# dual_vca_main.net
KiCad netlist of a schematic drawn in EAGLE
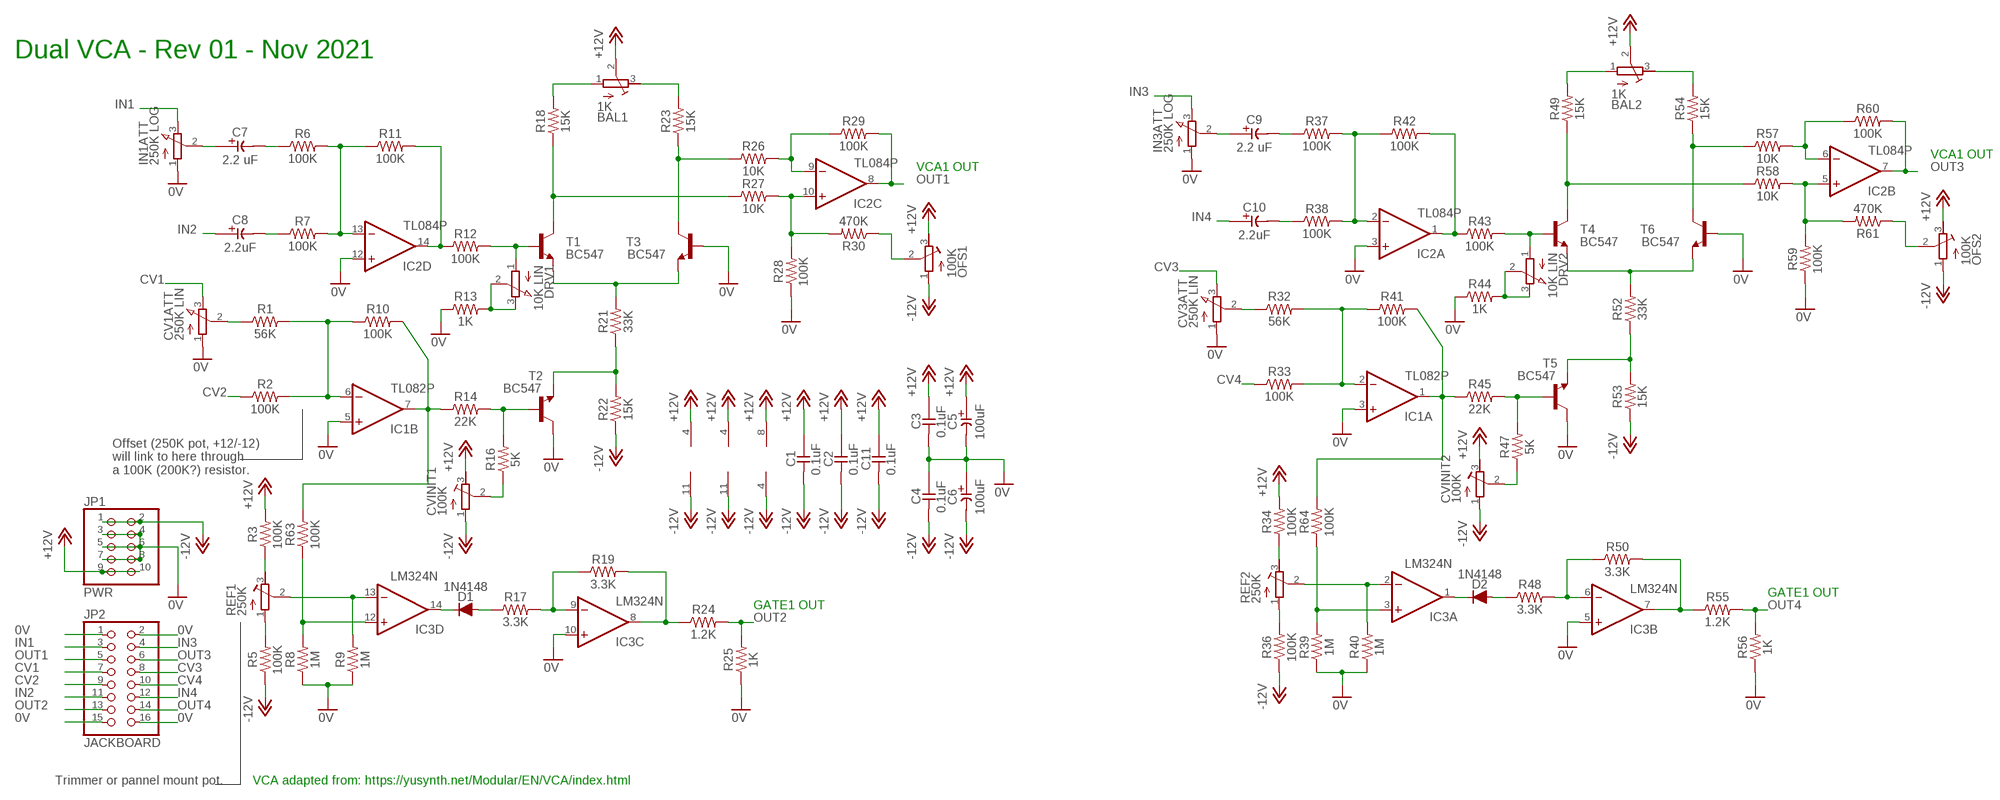
[diagram p0: schematic, sheet 1]

(export (version "E")
  (design (tool "Eeschema 10.0.6"))
  (components
    (comp (ref "BAL1")
      (value "1K")
      (footprint "eagle-import:RTRIM3339P")
      (libsource (lib "eagle-import") (part "R-TRIMM3339P"))
    )
    (comp (ref "BAL2")
      (value "1K")
      (footprint "eagle-import:RTRIM3339P")
      (libsource (lib "eagle-import") (part "R-TRIMM3339P"))
    )
    (comp (ref "C1")
      (value "0.1uF")
      (footprint "eagle-import:C025-024X044")
      (libsource (lib "eagle-import") (part "CC-US025-024X044"))
    )
    (comp (ref "C2")
      (value "0.1uF")
      (footprint "eagle-import:C025-024X044")
      (libsource (lib "eagle-import") (part "CC-US025-024X044"))
    )
    (comp (ref "C3")
      (value "0.1uF")
      (footprint "eagle-import:C025-024X044")
      (libsource (lib "eagle-import") (part "CC-US025-024X044"))
    )
    (comp (ref "C4")
      (value "0.1uF")
      (footprint "eagle-import:C025-024X044")
      (libsource (lib "eagle-import") (part "CC-US025-024X044"))
    )
    (comp (ref "C5")
      (value "100uF")
      (footprint "eagle-import:E5-8,5")
      (libsource (lib "eagle-import") (part "CE-USE5-8.5"))
    )
    (comp (ref "C6")
      (value "100uF")
      (footprint "eagle-import:E5-8,5")
      (libsource (lib "eagle-import") (part "CE-USE5-8.5"))
    )
    (comp (ref "C7")
      (value "2.2 uF")
      (footprint "eagle-import:E2-5")
      (libsource (lib "eagle-import") (part "CE-USE2-5"))
    )
    (comp (ref "C8")
      (value "2.2uF")
      (footprint "eagle-import:E2-5")
      (libsource (lib "eagle-import") (part "CE-USE2-5"))
    )
    (comp (ref "C9")
      (value "2.2 uF")
      (footprint "eagle-import:E2-5")
      (libsource (lib "eagle-import") (part "CE-USE2-5"))
    )
    (comp (ref "C10")
      (value "2.2uF")
      (footprint "eagle-import:E2-5")
      (libsource (lib "eagle-import") (part "CE-USE2-5"))
    )
    (comp (ref "C11")
      (value "0.1uF")
      (footprint "eagle-import:C025-024X044")
      (libsource (lib "eagle-import") (part "CC-US025-024X044"))
    )
    (comp (ref "CV1ATT")
      (value "250K LIN")
      (footprint "eagle-import:3RP_1610N")
      (libsource (lib "eagle-import") (part "3RP/1610N"))
    )
    (comp (ref "CV3ATT")
      (value "250K LIN")
      (footprint "eagle-import:3RP_1610N")
      (libsource (lib "eagle-import") (part "3RP/1610N"))
    )
    (comp (ref "CVINIT1")
      (value "100K")
      (footprint "eagle-import:RTRIM3339P")
      (libsource (lib "eagle-import") (part "R-TRIMM3339P"))
    )
    (comp (ref "CVINIT2")
      (value "100K")
      (footprint "eagle-import:RTRIM3339P")
      (libsource (lib "eagle-import") (part "R-TRIMM3339P"))
    )
    (comp (ref "D1")
      (value "1N4148")
      (footprint "eagle-import:DO34-5")
      (libsource (lib "eagle-import") (part "1N4148"))
    )
    (comp (ref "D2")
      (value "1N4148")
      (footprint "eagle-import:DO34-5")
      (libsource (lib "eagle-import") (part "1N4148"))
    )
    (comp (ref "DRV1")
      (value "10K LIN")
      (footprint "eagle-import:3RP_1610N")
      (libsource (lib "eagle-import") (part "3RP/1610N"))
    )
    (comp (ref "DRV2")
      (value "10K LIN")
      (footprint "eagle-import:3RP_1610N")
      (libsource (lib "eagle-import") (part "3RP/1610N"))
    )
    (comp (ref "IC1")
      (value "TL082P")
      (footprint "eagle-import:DIL08")
      (libsource (lib "eagle-import") (part "TL082P"))
    )
    (comp (ref "IC2")
      (value "TL084P")
      (footprint "eagle-import:DIL14")
      (libsource (lib "eagle-import") (part "TL084P"))
    )
    (comp (ref "IC3")
      (value "LM324N")
      (footprint "eagle-import:DIL14")
      (libsource (lib "eagle-import") (part "LM324N"))
    )
    (comp (ref "IN1ATT")
      (value "250K LOG")
      (footprint "eagle-import:3RP_1610N")
      (libsource (lib "eagle-import") (part "3RP/1610N"))
    )
    (comp (ref "IN3ATT")
      (value "250K LOG")
      (footprint "eagle-import:3RP_1610N")
      (libsource (lib "eagle-import") (part "3RP/1610N"))
    )
    (comp (ref "JP1")
      (value "PWR")
      (footprint "eagle-import:2X05")
      (libsource (lib "eagle-import") (part "PINHD-2X5"))
    )
    (comp (ref "JP2")
      (value "JACKBOARD")
      (footprint "eagle-import:2X08")
      (libsource (lib "eagle-import") (part "PINHD-2X8"))
    )
    (comp (ref "OFS1")
      (value "100K")
      (footprint "eagle-import:RTRIM3339P")
      (libsource (lib "eagle-import") (part "R-TRIMM3339P"))
    )
    (comp (ref "OFS2")
      (value "100K")
      (footprint "eagle-import:RTRIM3339P")
      (libsource (lib "eagle-import") (part "R-TRIMM3339P"))
    )
    (comp (ref "R1")
      (value "56K")
      (footprint "eagle-import:0207_7")
      (libsource (lib "eagle-import") (part "R"))
    )
    (comp (ref "R2")
      (value "100K")
      (footprint "eagle-import:0207_7")
      (libsource (lib "eagle-import") (part "R"))
    )
    (comp (ref "R3")
      (value "100K")
      (footprint "eagle-import:0207_7")
      (libsource (lib "eagle-import") (part "R"))
    )
    (comp (ref "R5")
      (value "100K")
      (footprint "eagle-import:0207_7")
      (libsource (lib "eagle-import") (part "R"))
    )
    (comp (ref "R6")
      (value "100K")
      (footprint "eagle-import:0207_7")
      (libsource (lib "eagle-import") (part "R"))
    )
    (comp (ref "R7")
      (value "100K")
      (footprint "eagle-import:0207_7")
      (libsource (lib "eagle-import") (part "R"))
    )
    (comp (ref "R8")
      (value "1M")
      (footprint "eagle-import:0207_7")
      (libsource (lib "eagle-import") (part "R"))
    )
    (comp (ref "R9")
      (value "1M")
      (footprint "eagle-import:0207_7")
      (libsource (lib "eagle-import") (part "R"))
    )
    (comp (ref "R10")
      (value "100K")
      (footprint "eagle-import:0207_7")
      (libsource (lib "eagle-import") (part "R"))
    )
    (comp (ref "R11")
      (value "100K")
      (footprint "eagle-import:0207_7")
      (libsource (lib "eagle-import") (part "R"))
    )
    (comp (ref "R12")
      (value "100K")
      (footprint "eagle-import:0207_7")
      (libsource (lib "eagle-import") (part "R"))
    )
    (comp (ref "R13")
      (value "1K")
      (footprint "eagle-import:0207_7")
      (libsource (lib "eagle-import") (part "R"))
    )
    (comp (ref "R14")
      (value "22K")
      (footprint "eagle-import:0207_7")
      (libsource (lib "eagle-import") (part "R"))
    )
    (comp (ref "R16")
      (value "5K")
      (footprint "eagle-import:0207_7")
      (libsource (lib "eagle-import") (part "R"))
    )
    (comp (ref "R17")
      (value "3.3K")
      (footprint "eagle-import:0207_7")
      (libsource (lib "eagle-import") (part "R"))
    )
    (comp (ref "R18")
      (value "15K")
      (footprint "eagle-import:0207_7")
      (libsource (lib "eagle-import") (part "R"))
    )
    (comp (ref "R19")
      (value "3.3K")
      (footprint "eagle-import:0207_7")
      (libsource (lib "eagle-import") (part "R"))
    )
    (comp (ref "R21")
      (value "33K")
      (footprint "eagle-import:0207_7")
      (libsource (lib "eagle-import") (part "R"))
    )
    (comp (ref "R22")
      (value "15K")
      (footprint "eagle-import:0207_7")
      (libsource (lib "eagle-import") (part "R"))
    )
    (comp (ref "R23")
      (value "15K")
      (footprint "eagle-import:0207_7")
      (libsource (lib "eagle-import") (part "R"))
    )
    (comp (ref "R24")
      (value "1.2K")
      (footprint "eagle-import:0207_7")
      (libsource (lib "eagle-import") (part "R"))
    )
    (comp (ref "R25")
      (value "1K")
      (footprint "eagle-import:0207_7")
      (libsource (lib "eagle-import") (part "R"))
    )
    (comp (ref "R26")
      (value "10K")
      (footprint "eagle-import:0207_7")
      (libsource (lib "eagle-import") (part "R"))
    )
    (comp (ref "R27")
      (value "10K")
      (footprint "eagle-import:0207_7")
      (libsource (lib "eagle-import") (part "R"))
    )
    (comp (ref "R28")
      (value "100K")
      (footprint "eagle-import:0207_7")
      (libsource (lib "eagle-import") (part "R"))
    )
    (comp (ref "R29")
      (value "100K")
      (footprint "eagle-import:0207_7")
      (libsource (lib "eagle-import") (part "R"))
    )
    (comp (ref "R30")
      (value "470K")
      (footprint "eagle-import:0207_7")
      (libsource (lib "eagle-import") (part "R"))
    )
    (comp (ref "R32")
      (value "56K")
      (footprint "eagle-import:0207_7")
      (libsource (lib "eagle-import") (part "R"))
    )
    (comp (ref "R33")
      (value "100K")
      (footprint "eagle-import:0207_7")
      (libsource (lib "eagle-import") (part "R"))
    )
    (comp (ref "R34")
      (value "100K")
      (footprint "eagle-import:0207_7")
      (libsource (lib "eagle-import") (part "R"))
    )
    (comp (ref "R36")
      (value "100K")
      (footprint "eagle-import:0207_7")
      (libsource (lib "eagle-import") (part "R"))
    )
    (comp (ref "R37")
      (value "100K")
      (footprint "eagle-import:0207_7")
      (libsource (lib "eagle-import") (part "R"))
    )
    (comp (ref "R38")
      (value "100K")
      (footprint "eagle-import:0207_7")
      (libsource (lib "eagle-import") (part "R"))
    )
    (comp (ref "R39")
      (value "1M")
      (footprint "eagle-import:0207_7")
      (libsource (lib "eagle-import") (part "R"))
    )
    (comp (ref "R40")
      (value "1M")
      (footprint "eagle-import:0207_7")
      (libsource (lib "eagle-import") (part "R"))
    )
    (comp (ref "R41")
      (value "100K")
      (footprint "eagle-import:0207_7")
      (libsource (lib "eagle-import") (part "R"))
    )
    (comp (ref "R42")
      (value "100K")
      (footprint "eagle-import:0207_7")
      (libsource (lib "eagle-import") (part "R"))
    )
    (comp (ref "R43")
      (value "100K")
      (footprint "eagle-import:0207_7")
      (libsource (lib "eagle-import") (part "R"))
    )
    (comp (ref "R44")
      (value "1K")
      (footprint "eagle-import:0207_7")
      (libsource (lib "eagle-import") (part "R"))
    )
    (comp (ref "R45")
      (value "22K")
      (footprint "eagle-import:0207_7")
      (libsource (lib "eagle-import") (part "R"))
    )
    (comp (ref "R47")
      (value "5K")
      (footprint "eagle-import:0207_7")
      (libsource (lib "eagle-import") (part "R"))
    )
    (comp (ref "R48")
      (value "3.3K")
      (footprint "eagle-import:0207_7")
      (libsource (lib "eagle-import") (part "R"))
    )
    (comp (ref "R49")
      (value "15K")
      (footprint "eagle-import:0207_7")
      (libsource (lib "eagle-import") (part "R"))
    )
    (comp (ref "R50")
      (value "3.3K")
      (footprint "eagle-import:0207_7")
      (libsource (lib "eagle-import") (part "R"))
    )
    (comp (ref "R52")
      (value "33K")
      (footprint "eagle-import:0207_7")
      (libsource (lib "eagle-import") (part "R"))
    )
    (comp (ref "R53")
      (value "15K")
      (footprint "eagle-import:0207_7")
      (libsource (lib "eagle-import") (part "R"))
    )
    (comp (ref "R54")
      (value "15K")
      (footprint "eagle-import:0207_7")
      (libsource (lib "eagle-import") (part "R"))
    )
    (comp (ref "R55")
      (value "1.2K")
      (footprint "eagle-import:0207_7")
      (libsource (lib "eagle-import") (part "R"))
    )
    (comp (ref "R56")
      (value "1K")
      (footprint "eagle-import:0207_7")
      (libsource (lib "eagle-import") (part "R"))
    )
    (comp (ref "R57")
      (value "10K")
      (footprint "eagle-import:0207_7")
      (libsource (lib "eagle-import") (part "R"))
    )
    (comp (ref "R58")
      (value "10K")
      (footprint "eagle-import:0207_7")
      (libsource (lib "eagle-import") (part "R"))
    )
    (comp (ref "R59")
      (value "100K")
      (footprint "eagle-import:0207_7")
      (libsource (lib "eagle-import") (part "R"))
    )
    (comp (ref "R60")
      (value "100K")
      (footprint "eagle-import:0207_7")
      (libsource (lib "eagle-import") (part "R"))
    )
    (comp (ref "R61")
      (value "470K")
      (footprint "eagle-import:0207_7")
      (libsource (lib "eagle-import") (part "R"))
    )
    (comp (ref "R63")
      (value "100K")
      (footprint "eagle-import:0207_7")
      (libsource (lib "eagle-import") (part "R"))
    )
    (comp (ref "R64")
      (value "100K")
      (footprint "eagle-import:0207_7")
      (libsource (lib "eagle-import") (part "R"))
    )
    (comp (ref "REF1")
      (value "250K")
      (footprint "eagle-import:RTRIM3339P")
      (libsource (lib "eagle-import") (part "R-TRIMM3339P"))
    )
    (comp (ref "REF2")
      (value "250K")
      (footprint "eagle-import:RTRIM3339P")
      (libsource (lib "eagle-import") (part "R-TRIMM3339P"))
    )
    (comp (ref "T1")
      (value "BC547")
      (footprint "eagle-import:TO92")
      (libsource (lib "eagle-import") (part "BC547"))
    )
    (comp (ref "T2")
      (value "BC547")
      (footprint "eagle-import:TO92")
      (libsource (lib "eagle-import") (part "BC547"))
    )
    (comp (ref "T3")
      (value "BC547")
      (footprint "eagle-import:TO92")
      (libsource (lib "eagle-import") (part "BC547"))
    )
    (comp (ref "T4")
      (value "BC547")
      (footprint "eagle-import:TO92")
      (libsource (lib "eagle-import") (part "BC547"))
    )
    (comp (ref "T5")
      (value "BC547")
      (footprint "eagle-import:TO92")
      (libsource (lib "eagle-import") (part "BC547"))
    )
    (comp (ref "T6")
      (value "BC547")
      (footprint "eagle-import:TO92")
      (libsource (lib "eagle-import") (part "BC547"))
    )
  )
  (nets
    (net (code "1") (name "+12V") (class "Default")
      (node (ref "BAL1") (pin "2") (pinfunction "S_2") (pintype "passive"))
      (node (ref "BAL2") (pin "2") (pinfunction "S_2") (pintype "passive"))
      (node (ref "C1") (pin "1") (pinfunction "1_1") (pintype "passive"))
      (node (ref "C11") (pin "1") (pinfunction "1_1") (pintype "passive"))
      (node (ref "C2") (pin "1") (pinfunction "1_1") (pintype "passive"))
      (node (ref "C3") (pin "1") (pinfunction "1_1") (pintype "passive"))
      (node (ref "C5") (pin "+") (pinfunction "+_+") (pintype "passive"))
      (node (ref "CVINIT1") (pin "3") (pinfunction "E_3") (pintype "passive"))
      (node (ref "CVINIT2") (pin "3") (pinfunction "E_3") (pintype "passive"))
      (node (ref "IC1") (pin "8") (pinfunction "V+_8") (pintype "power_in"))
      (node (ref "IC2") (pin "4") (pinfunction "V+_4") (pintype "power_in"))
      (node (ref "IC3") (pin "4") (pinfunction "V+_4") (pintype "power_in"))
      (node (ref "JP1") (pin "10") (pinfunction "10_10") (pintype "passive"))
      (node (ref "JP1") (pin "9") (pinfunction "9_9") (pintype "passive"))
      (node (ref "OFS1") (pin "3") (pinfunction "E_3") (pintype "passive"))
      (node (ref "OFS2") (pin "3") (pinfunction "E_3") (pintype "passive"))
      (node (ref "R3") (pin "2") (pinfunction "2_2") (pintype "passive"))
      (node (ref "R34") (pin "2") (pinfunction "2_2") (pintype "passive"))
    )
    (net (code "2") (name "-12V") (class "Default")
      (node (ref "C1") (pin "2") (pinfunction "2_2") (pintype "passive"))
      (node (ref "C11") (pin "2") (pinfunction "2_2") (pintype "passive"))
      (node (ref "C2") (pin "2") (pinfunction "2_2") (pintype "passive"))
      (node (ref "C4") (pin "2") (pinfunction "2_2") (pintype "passive"))
      (node (ref "C6") (pin "-") (pinfunction "-_-") (pintype "passive"))
      (node (ref "CVINIT1") (pin "1") (pinfunction "A_1") (pintype "passive"))
      (node (ref "CVINIT2") (pin "1") (pinfunction "A_1") (pintype "passive"))
      (node (ref "IC1") (pin "4") (pinfunction "V-_4") (pintype "power_in"))
      (node (ref "IC2") (pin "11") (pinfunction "V-_11") (pintype "power_in"))
      (node (ref "IC3") (pin "11") (pinfunction "V-_11") (pintype "power_in"))
      (node (ref "JP1") (pin "1") (pinfunction "1_1") (pintype "passive"))
      (node (ref "JP1") (pin "2") (pinfunction "2_2") (pintype "passive"))
      (node (ref "OFS1") (pin "1") (pinfunction "A_1") (pintype "passive"))
      (node (ref "OFS2") (pin "1") (pinfunction "A_1") (pintype "passive"))
      (node (ref "R22") (pin "1") (pinfunction "1_1") (pintype "passive"))
      (node (ref "R36") (pin "1") (pinfunction "1_1") (pintype "passive"))
      (node (ref "R5") (pin "1") (pinfunction "1_1") (pintype "passive"))
      (node (ref "R53") (pin "1") (pinfunction "1_1") (pintype "passive"))
    )
    (net (code "3") (name "/CV1") (class "Default")
      (node (ref "CV1ATT") (pin "3") (pinfunction "E_3") (pintype "passive"))
      (node (ref "JP2") (pin "7") (pinfunction "7_7") (pintype "passive"))
    )
    (net (code "4") (name "/CV2") (class "Default")
      (node (ref "JP2") (pin "9") (pinfunction "9_9") (pintype "passive"))
      (node (ref "R2") (pin "1") (pinfunction "1_1") (pintype "passive"))
    )
    (net (code "5") (name "/CV3") (class "Default")
      (node (ref "CV3ATT") (pin "3") (pinfunction "E_3") (pintype "passive"))
      (node (ref "JP2") (pin "8") (pinfunction "8_8") (pintype "passive"))
    )
    (net (code "6") (name "/CV4") (class "Default")
      (node (ref "JP2") (pin "10") (pinfunction "10_10") (pintype "passive"))
      (node (ref "R33") (pin "1") (pinfunction "1_1") (pintype "passive"))
    )
    (net (code "7") (name "/IN1") (class "Default")
      (node (ref "IN1ATT") (pin "3") (pinfunction "E_3") (pintype "passive"))
      (node (ref "JP2") (pin "3") (pinfunction "3_3") (pintype "passive"))
    )
    (net (code "8") (name "/IN2") (class "Default")
      (node (ref "C8") (pin "+") (pinfunction "+_+") (pintype "passive"))
      (node (ref "JP2") (pin "11") (pinfunction "11_11") (pintype "passive"))
    )
    (net (code "9") (name "/IN3") (class "Default")
      (node (ref "IN3ATT") (pin "3") (pinfunction "E_3") (pintype "passive"))
      (node (ref "JP2") (pin "4") (pinfunction "4_4") (pintype "passive"))
    )
    (net (code "10") (name "/IN4") (class "Default")
      (node (ref "C10") (pin "+") (pinfunction "+_+") (pintype "passive"))
      (node (ref "JP2") (pin "12") (pinfunction "12_12") (pintype "passive"))
    )
    (net (code "11") (name "/OUT1") (class "Default")
      (node (ref "IC2") (pin "8") (pinfunction "OUT_8") (pintype "output"))
      (node (ref "JP2") (pin "5") (pinfunction "5_5") (pintype "passive"))
      (node (ref "R29") (pin "2") (pinfunction "2_2") (pintype "passive"))
    )
    (net (code "12") (name "/OUT2") (class "Default")
      (node (ref "JP2") (pin "13") (pinfunction "13_13") (pintype "passive"))
      (node (ref "R24") (pin "2") (pinfunction "2_2") (pintype "passive"))
      (node (ref "R25") (pin "2") (pinfunction "2_2") (pintype "passive"))
    )
    (net (code "13") (name "/OUT3") (class "Default")
      (node (ref "IC2") (pin "7") (pinfunction "OUT_7") (pintype "output"))
      (node (ref "JP2") (pin "6") (pinfunction "6_6") (pintype "passive"))
      (node (ref "R60") (pin "2") (pinfunction "2_2") (pintype "passive"))
    )
    (net (code "14") (name "/OUT4") (class "Default")
      (node (ref "JP2") (pin "14") (pinfunction "14_14") (pintype "passive"))
      (node (ref "R55") (pin "2") (pinfunction "2_2") (pintype "passive"))
      (node (ref "R56") (pin "2") (pinfunction "2_2") (pintype "passive"))
    )
    (net (code "15") (name "0V") (class "Default")
      (node (ref "C3") (pin "2") (pinfunction "2_2") (pintype "passive"))
      (node (ref "C4") (pin "1") (pinfunction "1_1") (pintype "passive"))
      (node (ref "C5") (pin "-") (pinfunction "-_-") (pintype "passive"))
      (node (ref "C6") (pin "+") (pinfunction "+_+") (pintype "passive"))
      (node (ref "CV1ATT") (pin "1") (pinfunction "A_1") (pintype "passive"))
      (node (ref "CV3ATT") (pin "1") (pinfunction "A_1") (pintype "passive"))
      (node (ref "IC1") (pin "3") (pinfunction "+IN_3") (pintype "input"))
      (node (ref "IC1") (pin "5") (pinfunction "+IN_5") (pintype "input"))
      (node (ref "IC2") (pin "12") (pinfunction "+IN_12") (pintype "input"))
      (node (ref "IC2") (pin "3") (pinfunction "+IN_3") (pintype "input"))
      (node (ref "IC3") (pin "10") (pinfunction "+IN_10") (pintype "input"))
      (node (ref "IC3") (pin "5") (pinfunction "+IN_5") (pintype "input"))
      (node (ref "IN1ATT") (pin "1") (pinfunction "A_1") (pintype "passive"))
      (node (ref "IN3ATT") (pin "1") (pinfunction "A_1") (pintype "passive"))
      (node (ref "JP1") (pin "3") (pinfunction "3_3") (pintype "passive"))
      (node (ref "JP1") (pin "4") (pinfunction "4_4") (pintype "passive"))
      (node (ref "JP1") (pin "5") (pinfunction "5_5") (pintype "passive"))
      (node (ref "JP1") (pin "6") (pinfunction "6_6") (pintype "passive"))
      (node (ref "JP1") (pin "7") (pinfunction "7_7") (pintype "passive"))
      (node (ref "JP1") (pin "8") (pinfunction "8_8") (pintype "passive"))
      (node (ref "JP2") (pin "1") (pinfunction "1_1") (pintype "passive"))
      (node (ref "JP2") (pin "15") (pinfunction "15_15") (pintype "passive"))
      (node (ref "JP2") (pin "16") (pinfunction "16_16") (pintype "passive"))
      (node (ref "JP2") (pin "2") (pinfunction "2_2") (pintype "passive"))
      (node (ref "R13") (pin "1") (pinfunction "1_1") (pintype "passive"))
      (node (ref "R25") (pin "1") (pinfunction "1_1") (pintype "passive"))
      (node (ref "R28") (pin "1") (pinfunction "1_1") (pintype "passive"))
      (node (ref "R39") (pin "1") (pinfunction "1_1") (pintype "passive"))
      (node (ref "R40") (pin "1") (pinfunction "1_1") (pintype "passive"))
      (node (ref "R44") (pin "1") (pinfunction "1_1") (pintype "passive"))
      (node (ref "R56") (pin "1") (pinfunction "1_1") (pintype "passive"))
      (node (ref "R59") (pin "1") (pinfunction "1_1") (pintype "passive"))
      (node (ref "R8") (pin "1") (pinfunction "1_1") (pintype "passive"))
      (node (ref "R9") (pin "1") (pinfunction "1_1") (pintype "passive"))
      (node (ref "T2") (pin "3") (pinfunction "C_3") (pintype "passive"))
      (node (ref "T3") (pin "2") (pinfunction "B_2") (pintype "passive"))
      (node (ref "T5") (pin "3") (pinfunction "C_3") (pintype "passive"))
      (node (ref "T6") (pin "2") (pinfunction "B_2") (pintype "passive"))
    )
    (net (code "16") (name "Net-(BAL1-A)") (class "Default")
      (node (ref "BAL1") (pin "1") (pinfunction "A_1") (pintype "passive"))
      (node (ref "R18") (pin "2") (pinfunction "2_2") (pintype "passive"))
    )
    (net (code "17") (name "Net-(BAL1-E)") (class "Default")
      (node (ref "BAL1") (pin "3") (pinfunction "E_3") (pintype "passive"))
      (node (ref "R23") (pin "2") (pinfunction "2_2") (pintype "passive"))
    )
    (net (code "18") (name "Net-(BAL2-A)") (class "Default")
      (node (ref "BAL2") (pin "1") (pinfunction "A_1") (pintype "passive"))
      (node (ref "R49") (pin "2") (pinfunction "2_2") (pintype "passive"))
    )
    (net (code "19") (name "Net-(BAL2-E)") (class "Default")
      (node (ref "BAL2") (pin "3") (pinfunction "E_3") (pintype "passive"))
      (node (ref "R54") (pin "2") (pinfunction "2_2") (pintype "passive"))
    )
    (net (code "20") (name "Net-(C7-Pad-)") (class "Default")
      (node (ref "C7") (pin "-") (pinfunction "-_-") (pintype "passive"))
      (node (ref "R6") (pin "1") (pinfunction "1_1") (pintype "passive"))
    )
    (net (code "21") (name "Net-(C8-Pad-)") (class "Default")
      (node (ref "C8") (pin "-") (pinfunction "-_-") (pintype "passive"))
      (node (ref "R7") (pin "1") (pinfunction "1_1") (pintype "passive"))
    )
    (net (code "22") (name "Net-(C9-Pad-)") (class "Default")
      (node (ref "C9") (pin "-") (pinfunction "-_-") (pintype "passive"))
      (node (ref "R37") (pin "1") (pinfunction "1_1") (pintype "passive"))
    )
    (net (code "23") (name "Net-(C10-Pad-)") (class "Default")
      (node (ref "C10") (pin "-") (pinfunction "-_-") (pintype "passive"))
      (node (ref "R38") (pin "1") (pinfunction "1_1") (pintype "passive"))
    )
    (net (code "24") (name "Net-(CV1ATT-S)") (class "Default")
      (node (ref "CV1ATT") (pin "2") (pinfunction "S_2") (pintype "passive"))
      (node (ref "R1") (pin "1") (pinfunction "1_1") (pintype "passive"))
    )
    (net (code "25") (name "Net-(CV3ATT-S)") (class "Default")
      (node (ref "CV3ATT") (pin "2") (pinfunction "S_2") (pintype "passive"))
      (node (ref "R32") (pin "1") (pinfunction "1_1") (pintype "passive"))
    )
    (net (code "26") (name "Net-(CVINIT1-S)") (class "Default")
      (node (ref "CVINIT1") (pin "2") (pinfunction "S_2") (pintype "passive"))
      (node (ref "R16") (pin "1") (pinfunction "1_1") (pintype "passive"))
    )
    (net (code "27") (name "Net-(CVINIT2-S)") (class "Default")
      (node (ref "CVINIT2") (pin "2") (pinfunction "S_2") (pintype "passive"))
      (node (ref "R47") (pin "1") (pinfunction "1_1") (pintype "passive"))
    )
    (net (code "28") (name "Net-(D1-PadA)") (class "Default")
      (node (ref "D1") (pin "A") (pinfunction "A_A") (pintype "passive"))
      (node (ref "R17") (pin "1") (pinfunction "1_1") (pintype "passive"))
    )
    (net (code "29") (name "Net-(D2-PadA)") (class "Default")
      (node (ref "D2") (pin "A") (pinfunction "A_A") (pintype "passive"))
      (node (ref "R48") (pin "1") (pinfunction "1_1") (pintype "passive"))
    )
    (net (code "30") (name "Net-(DRV1-A)") (class "Default")
      (node (ref "DRV1") (pin "1") (pinfunction "A_1") (pintype "passive"))
      (node (ref "R12") (pin "2") (pinfunction "2_2") (pintype "passive"))
      (node (ref "T1") (pin "2") (pinfunction "B_2") (pintype "passive"))
    )
    (net (code "31") (name "Net-(DRV1-E)") (class "Default")
      (node (ref "DRV1") (pin "2") (pinfunction "S_2") (pintype "passive"))
      (node (ref "DRV1") (pin "3") (pinfunction "E_3") (pintype "passive"))
      (node (ref "R13") (pin "2") (pinfunction "2_2") (pintype "passive"))
    )
    (net (code "32") (name "Net-(DRV2-A)") (class "Default")
      (node (ref "DRV2") (pin "1") (pinfunction "A_1") (pintype "passive"))
      (node (ref "R43") (pin "2") (pinfunction "2_2") (pintype "passive"))
      (node (ref "T4") (pin "2") (pinfunction "B_2") (pintype "passive"))
    )
    (net (code "33") (name "Net-(DRV2-E)") (class "Default")
      (node (ref "DRV2") (pin "2") (pinfunction "S_2") (pintype "passive"))
      (node (ref "DRV2") (pin "3") (pinfunction "E_3") (pintype "passive"))
      (node (ref "R44") (pin "2") (pinfunction "2_2") (pintype "passive"))
    )
    (net (code "34") (name "Net-(IC1A--IN)") (class "Default")
      (node (ref "IC1") (pin "2") (pinfunction "-IN_2") (pintype "input"))
      (node (ref "R32") (pin "2") (pinfunction "2_2") (pintype "passive"))
      (node (ref "R33") (pin "2") (pinfunction "2_2") (pintype "passive"))
      (node (ref "R41") (pin "1") (pinfunction "1_1") (pintype "passive"))
    )
    (net (code "35") (name "Net-(IC1A-OUT)") (class "Default")
      (node (ref "IC1") (pin "1") (pinfunction "OUT_1") (pintype "output"))
      (node (ref "R41") (pin "2") (pinfunction "2_2") (pintype "passive"))
      (node (ref "R45") (pin "1") (pinfunction "1_1") (pintype "passive"))
      (node (ref "R64") (pin "2") (pinfunction "2_2") (pintype "passive"))
    )
    (net (code "36") (name "Net-(IC1B--IN)") (class "Default")
      (node (ref "IC1") (pin "6") (pinfunction "-IN_6") (pintype "input"))
      (node (ref "R1") (pin "2") (pinfunction "2_2") (pintype "passive"))
      (node (ref "R10") (pin "1") (pinfunction "1_1") (pintype "passive"))
      (node (ref "R2") (pin "2") (pinfunction "2_2") (pintype "passive"))
    )
    (net (code "37") (name "Net-(IC1B-OUT)") (class "Default")
      (node (ref "IC1") (pin "7") (pinfunction "OUT_7") (pintype "output"))
      (node (ref "R10") (pin "2") (pinfunction "2_2") (pintype "passive"))
      (node (ref "R14") (pin "1") (pinfunction "1_1") (pintype "passive"))
      (node (ref "R63") (pin "2") (pinfunction "2_2") (pintype "passive"))
    )
    (net (code "38") (name "Net-(IC2A--IN)") (class "Default")
      (node (ref "IC2") (pin "2") (pinfunction "-IN_2") (pintype "input"))
      (node (ref "R37") (pin "2") (pinfunction "2_2") (pintype "passive"))
      (node (ref "R38") (pin "2") (pinfunction "2_2") (pintype "passive"))
      (node (ref "R42") (pin "1") (pinfunction "1_1") (pintype "passive"))
    )
    (net (code "39") (name "Net-(IC2A-OUT)") (class "Default")
      (node (ref "IC2") (pin "1") (pinfunction "OUT_1") (pintype "output"))
      (node (ref "R42") (pin "2") (pinfunction "2_2") (pintype "passive"))
      (node (ref "R43") (pin "1") (pinfunction "1_1") (pintype "passive"))
    )
    (net (code "40") (name "Net-(IC2B-+IN)") (class "Default")
      (node (ref "IC2") (pin "5") (pinfunction "+IN_5") (pintype "input"))
      (node (ref "R58") (pin "2") (pinfunction "2_2") (pintype "passive"))
      (node (ref "R59") (pin "2") (pinfunction "2_2") (pintype "passive"))
      (node (ref "R61") (pin "2") (pinfunction "2_2") (pintype "passive"))
    )
    (net (code "41") (name "Net-(IC2B--IN)") (class "Default")
      (node (ref "IC2") (pin "6") (pinfunction "-IN_6") (pintype "input"))
      (node (ref "R57") (pin "2") (pinfunction "2_2") (pintype "passive"))
      (node (ref "R60") (pin "1") (pinfunction "1_1") (pintype "passive"))
    )
    (net (code "42") (name "Net-(IC2C-+IN)") (class "Default")
      (node (ref "IC2") (pin "10") (pinfunction "+IN_10") (pintype "input"))
      (node (ref "R27") (pin "2") (pinfunction "2_2") (pintype "passive"))
      (node (ref "R28") (pin "2") (pinfunction "2_2") (pintype "passive"))
      (node (ref "R30") (pin "2") (pinfunction "2_2") (pintype "passive"))
    )
    (net (code "43") (name "Net-(IC2C--IN)") (class "Default")
      (node (ref "IC2") (pin "9") (pinfunction "-IN_9") (pintype "input"))
      (node (ref "R26") (pin "2") (pinfunction "2_2") (pintype "passive"))
      (node (ref "R29") (pin "1") (pinfunction "1_1") (pintype "passive"))
    )
    (net (code "44") (name "Net-(IC2D--IN)") (class "Default")
      (node (ref "IC2") (pin "13") (pinfunction "-IN_13") (pintype "input"))
      (node (ref "R11") (pin "1") (pinfunction "1_1") (pintype "passive"))
      (node (ref "R6") (pin "2") (pinfunction "2_2") (pintype "passive"))
      (node (ref "R7") (pin "2") (pinfunction "2_2") (pintype "passive"))
    )
    (net (code "45") (name "Net-(IC2D-OUT)") (class "Default")
      (node (ref "IC2") (pin "14") (pinfunction "OUT_14") (pintype "output"))
      (node (ref "R11") (pin "2") (pinfunction "2_2") (pintype "passive"))
      (node (ref "R12") (pin "1") (pinfunction "1_1") (pintype "passive"))
    )
    (net (code "46") (name "Net-(IC3A-+IN)") (class "Default")
      (node (ref "IC3") (pin "3") (pinfunction "+IN_3") (pintype "input"))
      (node (ref "R39") (pin "2") (pinfunction "2_2") (pintype "passive"))
      (node (ref "R64") (pin "1") (pinfunction "1_1") (pintype "passive"))
    )
    (net (code "47") (name "Net-(IC3A--IN)") (class "Default")
      (node (ref "IC3") (pin "2") (pinfunction "-IN_2") (pintype "input"))
      (node (ref "R40") (pin "2") (pinfunction "2_2") (pintype "passive"))
      (node (ref "REF2") (pin "2") (pinfunction "S_2") (pintype "passive"))
    )
    (net (code "48") (name "Net-(IC3A-OUT)") (class "Default")
      (node (ref "D2") (pin "C") (pinfunction "C_C") (pintype "passive"))
      (node (ref "IC3") (pin "1") (pinfunction "OUT_1") (pintype "output"))
    )
    (net (code "49") (name "Net-(IC3B--IN)") (class "Default")
      (node (ref "IC3") (pin "6") (pinfunction "-IN_6") (pintype "input"))
      (node (ref "R48") (pin "2") (pinfunction "2_2") (pintype "passive"))
      (node (ref "R50") (pin "1") (pinfunction "1_1") (pintype "passive"))
    )
    (net (code "50") (name "Net-(IC3B-OUT)") (class "Default")
      (node (ref "IC3") (pin "7") (pinfunction "OUT_7") (pintype "output"))
      (node (ref "R50") (pin "2") (pinfunction "2_2") (pintype "passive"))
      (node (ref "R55") (pin "1") (pinfunction "1_1") (pintype "passive"))
    )
    (net (code "51") (name "Net-(IC3C--IN)") (class "Default")
      (node (ref "IC3") (pin "9") (pinfunction "-IN_9") (pintype "input"))
      (node (ref "R17") (pin "2") (pinfunction "2_2") (pintype "passive"))
      (node (ref "R19") (pin "1") (pinfunction "1_1") (pintype "passive"))
    )
    (net (code "52") (name "Net-(IC3C-OUT)") (class "Default")
      (node (ref "IC3") (pin "8") (pinfunction "OUT_8") (pintype "output"))
      (node (ref "R19") (pin "2") (pinfunction "2_2") (pintype "passive"))
      (node (ref "R24") (pin "1") (pinfunction "1_1") (pintype "passive"))
    )
    (net (code "53") (name "Net-(IC3D-+IN)") (class "Default")
      (node (ref "IC3") (pin "12") (pinfunction "+IN_12") (pintype "input"))
      (node (ref "R63") (pin "1") (pinfunction "1_1") (pintype "passive"))
      (node (ref "R8") (pin "2") (pinfunction "2_2") (pintype "passive"))
    )
    (net (code "54") (name "Net-(IC3D--IN)") (class "Default")
      (node (ref "IC3") (pin "13") (pinfunction "-IN_13") (pintype "input"))
      (node (ref "R9") (pin "2") (pinfunction "2_2") (pintype "passive"))
      (node (ref "REF1") (pin "2") (pinfunction "S_2") (pintype "passive"))
    )
    (net (code "55") (name "Net-(IC3D-OUT)") (class "Default")
      (node (ref "D1") (pin "C") (pinfunction "C_C") (pintype "passive"))
      (node (ref "IC3") (pin "14") (pinfunction "OUT_14") (pintype "output"))
    )
    (net (code "56") (name "Net-(IN1ATT-S)") (class "Default")
      (node (ref "C7") (pin "+") (pinfunction "+_+") (pintype "passive"))
      (node (ref "IN1ATT") (pin "2") (pinfunction "S_2") (pintype "passive"))
    )
    (net (code "57") (name "Net-(IN3ATT-S)") (class "Default")
      (node (ref "C9") (pin "+") (pinfunction "+_+") (pintype "passive"))
      (node (ref "IN3ATT") (pin "2") (pinfunction "S_2") (pintype "passive"))
    )
    (net (code "58") (name "Net-(OFS1-S)") (class "Default")
      (node (ref "OFS1") (pin "2") (pinfunction "S_2") (pintype "passive"))
      (node (ref "R30") (pin "1") (pinfunction "1_1") (pintype "passive"))
    )
    (net (code "59") (name "Net-(OFS2-S)") (class "Default")
      (node (ref "OFS2") (pin "2") (pinfunction "S_2") (pintype "passive"))
      (node (ref "R61") (pin "1") (pinfunction "1_1") (pintype "passive"))
    )
    (net (code "60") (name "Net-(REF1-A)") (class "Default")
      (node (ref "R5") (pin "2") (pinfunction "2_2") (pintype "passive"))
      (node (ref "REF1") (pin "1") (pinfunction "A_1") (pintype "passive"))
    )
    (net (code "61") (name "Net-(REF1-E)") (class "Default")
      (node (ref "R3") (pin "1") (pinfunction "1_1") (pintype "passive"))
      (node (ref "REF1") (pin "3") (pinfunction "E_3") (pintype "passive"))
    )
    (net (code "62") (name "Net-(REF2-A)") (class "Default")
      (node (ref "R36") (pin "2") (pinfunction "2_2") (pintype "passive"))
      (node (ref "REF2") (pin "1") (pinfunction "A_1") (pintype "passive"))
    )
    (net (code "63") (name "Net-(REF2-E)") (class "Default")
      (node (ref "R34") (pin "1") (pinfunction "1_1") (pintype "passive"))
      (node (ref "REF2") (pin "3") (pinfunction "E_3") (pintype "passive"))
    )
    (net (code "64") (name "Net-(T1-C)") (class "Default")
      (node (ref "R18") (pin "1") (pinfunction "1_1") (pintype "passive"))
      (node (ref "R27") (pin "1") (pinfunction "1_1") (pintype "passive"))
      (node (ref "T1") (pin "3") (pinfunction "C_3") (pintype "passive"))
    )
    (net (code "65") (name "Net-(T1-E)") (class "Default")
      (node (ref "R21") (pin "2") (pinfunction "2_2") (pintype "passive"))
      (node (ref "T1") (pin "1") (pinfunction "E_1") (pintype "passive"))
      (node (ref "T3") (pin "1") (pinfunction "E_1") (pintype "passive"))
    )
    (net (code "66") (name "Net-(T2-B)") (class "Default")
      (node (ref "R14") (pin "2") (pinfunction "2_2") (pintype "passive"))
      (node (ref "R16") (pin "2") (pinfunction "2_2") (pintype "passive"))
      (node (ref "T2") (pin "2") (pinfunction "B_2") (pintype "passive"))
    )
    (net (code "67") (name "Net-(T2-E)") (class "Default")
      (node (ref "R21") (pin "1") (pinfunction "1_1") (pintype "passive"))
      (node (ref "R22") (pin "2") (pinfunction "2_2") (pintype "passive"))
      (node (ref "T2") (pin "1") (pinfunction "E_1") (pintype "passive"))
    )
    (net (code "68") (name "Net-(T3-C)") (class "Default")
      (node (ref "R23") (pin "1") (pinfunction "1_1") (pintype "passive"))
      (node (ref "R26") (pin "1") (pinfunction "1_1") (pintype "passive"))
      (node (ref "T3") (pin "3") (pinfunction "C_3") (pintype "passive"))
    )
    (net (code "69") (name "Net-(T4-C)") (class "Default")
      (node (ref "R49") (pin "1") (pinfunction "1_1") (pintype "passive"))
      (node (ref "R58") (pin "1") (pinfunction "1_1") (pintype "passive"))
      (node (ref "T4") (pin "3") (pinfunction "C_3") (pintype "passive"))
    )
    (net (code "70") (name "Net-(T4-E)") (class "Default")
      (node (ref "R52") (pin "2") (pinfunction "2_2") (pintype "passive"))
      (node (ref "T4") (pin "1") (pinfunction "E_1") (pintype "passive"))
      (node (ref "T6") (pin "1") (pinfunction "E_1") (pintype "passive"))
    )
    (net (code "71") (name "Net-(T5-B)") (class "Default")
      (node (ref "R45") (pin "2") (pinfunction "2_2") (pintype "passive"))
      (node (ref "R47") (pin "2") (pinfunction "2_2") (pintype "passive"))
      (node (ref "T5") (pin "2") (pinfunction "B_2") (pintype "passive"))
    )
    (net (code "72") (name "Net-(T5-E)") (class "Default")
      (node (ref "R52") (pin "1") (pinfunction "1_1") (pintype "passive"))
      (node (ref "R53") (pin "2") (pinfunction "2_2") (pintype "passive"))
      (node (ref "T5") (pin "1") (pinfunction "E_1") (pintype "passive"))
    )
    (net (code "73") (name "Net-(T6-C)") (class "Default")
      (node (ref "R54") (pin "1") (pinfunction "1_1") (pintype "passive"))
      (node (ref "R57") (pin "1") (pinfunction "1_1") (pintype "passive"))
      (node (ref "T6") (pin "3") (pinfunction "C_3") (pintype "passive"))
    )
  )
)
